# CAN.net
KiCad netlist of a schematic drawn in Altium Designer
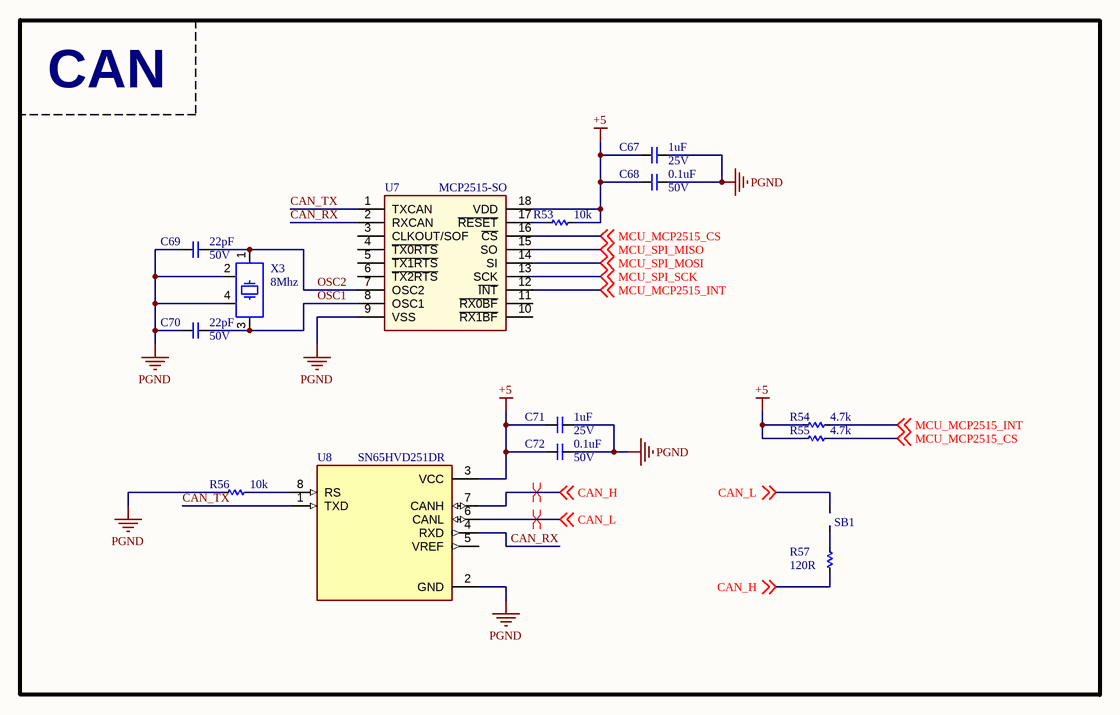
[diagram p0: CAN.SchDoc]

(export (version "E")
  (design (tool "Eeschema 10.0.6"))
  (components
    (comp (ref "C67")
      (value "1uF")
      (footprint "CAP_C_1608X80")
      (description "CAP")
      (fields (field (name "VOLTAGE") "25V"))
      (libsource (lib "LABLIB") (part "_CAP_C_2"))
    )
    (comp (ref "C68")
      (value "0.1uF")
      (footprint "CAP_C_1608X80")
      (description "CAP")
      (fields (field (name "VOLTAGE") "50V"))
      (libsource (lib "LABLIB") (part "_CAP_C_2"))
    )
    (comp (ref "C69")
      (value "22pF")
      (footprint "CAP_C_1608X80")
      (description "CAP")
      (fields (field (name "VOLTAGE") "50V"))
      (libsource (lib "LABLIB") (part "_CAP_C_2"))
    )
    (comp (ref "C70")
      (value "22pF")
      (footprint "CAP_C_1608X80")
      (description "CAP")
      (fields (field (name "VOLTAGE") "50V"))
      (libsource (lib "LABLIB") (part "_CAP_C_2"))
    )
    (comp (ref "C71")
      (value "1uF")
      (footprint "CAP_C_1608X80")
      (description "CAP")
      (fields (field (name "VOLTAGE") "25V"))
      (libsource (lib "LABLIB") (part "_CAP_C_2"))
    )
    (comp (ref "C72")
      (value "0.1uF")
      (footprint "CAP_C_1608X80")
      (description "CAP")
      (fields (field (name "VOLTAGE") "50V"))
      (libsource (lib "LABLIB") (part "_CAP_C_2"))
    )
    (comp (ref "R53")
      (value "10k")
      (footprint "RES_C_1608X60")
      (description "RES")
      (libsource (lib "LABLIB") (part "_RES_B_2_2"))
    )
    (comp (ref "R54")
      (value "4.7k")
      (footprint "RES_C_1608X60")
      (description "RES")
      (libsource (lib "LABLIB") (part "_RES_B_2_2"))
    )
    (comp (ref "R55")
      (value "4.7k")
      (footprint "RES_C_1608X60")
      (description "RES")
      (libsource (lib "LABLIB") (part "_RES_B_2_2"))
    )
    (comp (ref "R56")
      (value "10k")
      (footprint "RES_C_1608X60")
      (description "RES")
      (libsource (lib "LABLIB") (part "_RES_B_2_2"))
    )
    (comp (ref "R57")
      (value "120R")
      (footprint "RES_C_1608X60")
      (description "RES")
      (libsource (lib "LABLIB") (part "_RES_B_2_2"))
    )
    (comp (ref "SB1") (value "N/A") (footprint "JUMPER_1608") (libsource (lib "LV") (part "JUMPER")))
    (comp (ref "U7")
      (value "MCP2515-SO")
      (footprint "SOIC-20")
      (description "Stand-Alone CAN Controller with SPI Interface")
      (libsource (lib "KIENASIY123_LIB") (part "MCP2515-SO"))
    )
    (comp (ref "U8")
      (value "SN65HVD251DR")
      (footprint "SOIC-8")
      (libsource (lib "KIENASIY123_LIB") (part "SN65HVD251DR"))
    )
    (comp (ref "X3")
      (value "8Mhz")
      (footprint "XTAL_3225")
      (libsource (lib "KIENASIY123_LIB") (part "crystal_4pin"))
    )
  )
  (nets
    (net (code "1") (name "+5") (class "Default")
      (node (ref "C67") (pin "1") (pinfunction "1_1") (pintype "passive"))
      (node (ref "C68") (pin "1") (pinfunction "1_1") (pintype "passive"))
      (node (ref "C71") (pin "2") (pinfunction "2_2") (pintype "passive"))
      (node (ref "C72") (pin "1") (pinfunction "1_1") (pintype "passive"))
      (node (ref "R53") (pin "2") (pinfunction "2_2") (pintype "passive"))
      (node (ref "R54") (pin "1") (pinfunction "1_1") (pintype "passive"))
      (node (ref "R55") (pin "1") (pinfunction "1_1") (pintype "passive"))
      (node (ref "U7") (pin "18") (pinfunction "VDD_18") (pintype "passive"))
      (node (ref "U8") (pin "3") (pinfunction "VCC_3") (pintype "power_in"))
    )
    (net (code "2") (name "/CAN_RX") (class "Default")
      (node (ref "U7") (pin "2") (pinfunction "RXCAN_2") (pintype "passive"))
      (node (ref "U8") (pin "4") (pinfunction "RXD_4") (pintype "output"))
    )
    (net (code "3") (name "/CAN_TX") (class "Default")
      (node (ref "U7") (pin "1") (pinfunction "TXCAN_1") (pintype "passive"))
      (node (ref "U8") (pin "1") (pinfunction "TXD_1") (pintype "input"))
    )
    (net (code "4") (name "/OSC1") (class "Default")
      (node (ref "C70") (pin "1") (pinfunction "1_1") (pintype "passive"))
      (node (ref "U7") (pin "8") (pinfunction "OSC1_8") (pintype "passive"))
      (node (ref "X3") (pin "3") (pinfunction "3_3") (pintype "passive"))
    )
    (net (code "5") (name "/OSC2") (class "Default")
      (node (ref "C69") (pin "1") (pinfunction "1_1") (pintype "passive"))
      (node (ref "U7") (pin "7") (pinfunction "OSC2_7") (pintype "passive"))
      (node (ref "X3") (pin "1") (pinfunction "1_1") (pintype "passive"))
    )
    (net (code "6") (name "CAN_H") (class "Default")
      (node (ref "R57") (pin "1") (pinfunction "1_1") (pintype "passive"))
      (node (ref "U8") (pin "7") (pinfunction "CANH_7") (pintype "bidirectional"))
    )
    (net (code "7") (name "CAN_L") (class "Default")
      (node (ref "SB1") (pin "1") (pinfunction "1_1") (pintype "passive"))
      (node (ref "U8") (pin "6") (pinfunction "CANL_6") (pintype "bidirectional"))
    )
    (net (code "8") (name "MCU_MCP2515_CS") (class "Default")
      (node (ref "R55") (pin "2") (pinfunction "2_2") (pintype "passive"))
      (node (ref "U7") (pin "16") (pinfunction "~{CS}_16") (pintype "passive"))
    )
    (net (code "9") (name "MCU_MCP2515_INT") (class "Default")
      (node (ref "R54") (pin "2") (pinfunction "2_2") (pintype "passive"))
      (node (ref "U7") (pin "12") (pinfunction "~{INT}_12") (pintype "passive"))
    )
    (net (code "10") (name "MCU_SPI_MISO") (class "Default")
      (node (ref "U7") (pin "15") (pinfunction "SO_15") (pintype "passive"))
    )
    (net (code "11") (name "MCU_SPI_MOSI") (class "Default")
      (node (ref "U7") (pin "14") (pinfunction "SI_14") (pintype "passive"))
    )
    (net (code "12") (name "MCU_SPI_SCK") (class "Default")
      (node (ref "U7") (pin "13") (pinfunction "SCK_13") (pintype "passive"))
    )
    (net (code "13") (name "Net-(R57-Pad2)") (class "Default")
      (node (ref "R57") (pin "2") (pinfunction "2_2") (pintype "passive"))
      (node (ref "SB1") (pin "2") (pinfunction "2_2") (pintype "passive"))
    )
    (net (code "14") (name "Net-(U7-~{RESET})") (class "Default")
      (node (ref "R53") (pin "1") (pinfunction "1_1") (pintype "passive"))
      (node (ref "U7") (pin "17") (pinfunction "~{RESET}_17") (pintype "passive"))
    )
    (net (code "15") (name "Net-(U8-RS)") (class "Default")
      (node (ref "R56") (pin "2") (pinfunction "2_2") (pintype "passive"))
      (node (ref "U8") (pin "8") (pinfunction "RS_8") (pintype "input"))
    )
    (net (code "16") (name "PGND") (class "Default")
      (node (ref "C67") (pin "2") (pinfunction "2_2") (pintype "passive"))
      (node (ref "C68") (pin "2") (pinfunction "2_2") (pintype "passive"))
      (node (ref "C69") (pin "2") (pinfunction "2_2") (pintype "passive"))
      (node (ref "C70") (pin "2") (pinfunction "2_2") (pintype "passive"))
      (node (ref "C71") (pin "1") (pinfunction "1_1") (pintype "passive"))
      (node (ref "C72") (pin "2") (pinfunction "2_2") (pintype "passive"))
      (node (ref "R56") (pin "1") (pinfunction "1_1") (pintype "passive"))
      (node (ref "U7") (pin "9") (pinfunction "VSS_9") (pintype "passive"))
      (node (ref "U8") (pin "2") (pinfunction "GND_2") (pintype "power_in"))
      (node (ref "X3") (pin "2") (pinfunction "2_2") (pintype "passive"))
      (node (ref "X3") (pin "4") (pinfunction "4_4") (pintype "passive"))
    )
    (net (code "17") (name "unconnected-(U7-CLKOUT{slash}SOF-Pad3)") (class "Default")
      (node (ref "U7") (pin "3") (pinfunction "CLKOUT/SOF_3") (pintype "passive"))
    )
    (net (code "18") (name "unconnected-(U7-~{RX0BF}-Pad11)") (class "Default")
      (node (ref "U7") (pin "11") (pinfunction "~{RX0BF}_11") (pintype "passive"))
    )
    (net (code "19") (name "unconnected-(U7-~{RX1BF}-Pad10)") (class "Default")
      (node (ref "U7") (pin "10") (pinfunction "~{RX1BF}_10") (pintype "passive"))
    )
    (net (code "20") (name "unconnected-(U7-~{TX0RTS}-Pad4)") (class "Default")
      (node (ref "U7") (pin "4") (pinfunction "~{TX0RTS}_4") (pintype "passive"))
    )
    (net (code "21") (name "unconnected-(U7-~{TX1RTS}-Pad5)") (class "Default")
      (node (ref "U7") (pin "5") (pinfunction "~{TX1RTS}_5") (pintype "passive"))
    )
    (net (code "22") (name "unconnected-(U7-~{TX2RTS}-Pad6)") (class "Default")
      (node (ref "U7") (pin "6") (pinfunction "~{TX2RTS}_6") (pintype "passive"))
    )
    (net (code "23") (name "unconnected-(U8-VREF-Pad5)") (class "Default")
      (node (ref "U8") (pin "5") (pinfunction "VREF_5") (pintype "output"))
    )
  )
)
